# amp128-v5.net
KiCad netlist of a schematic drawn in EAGLE
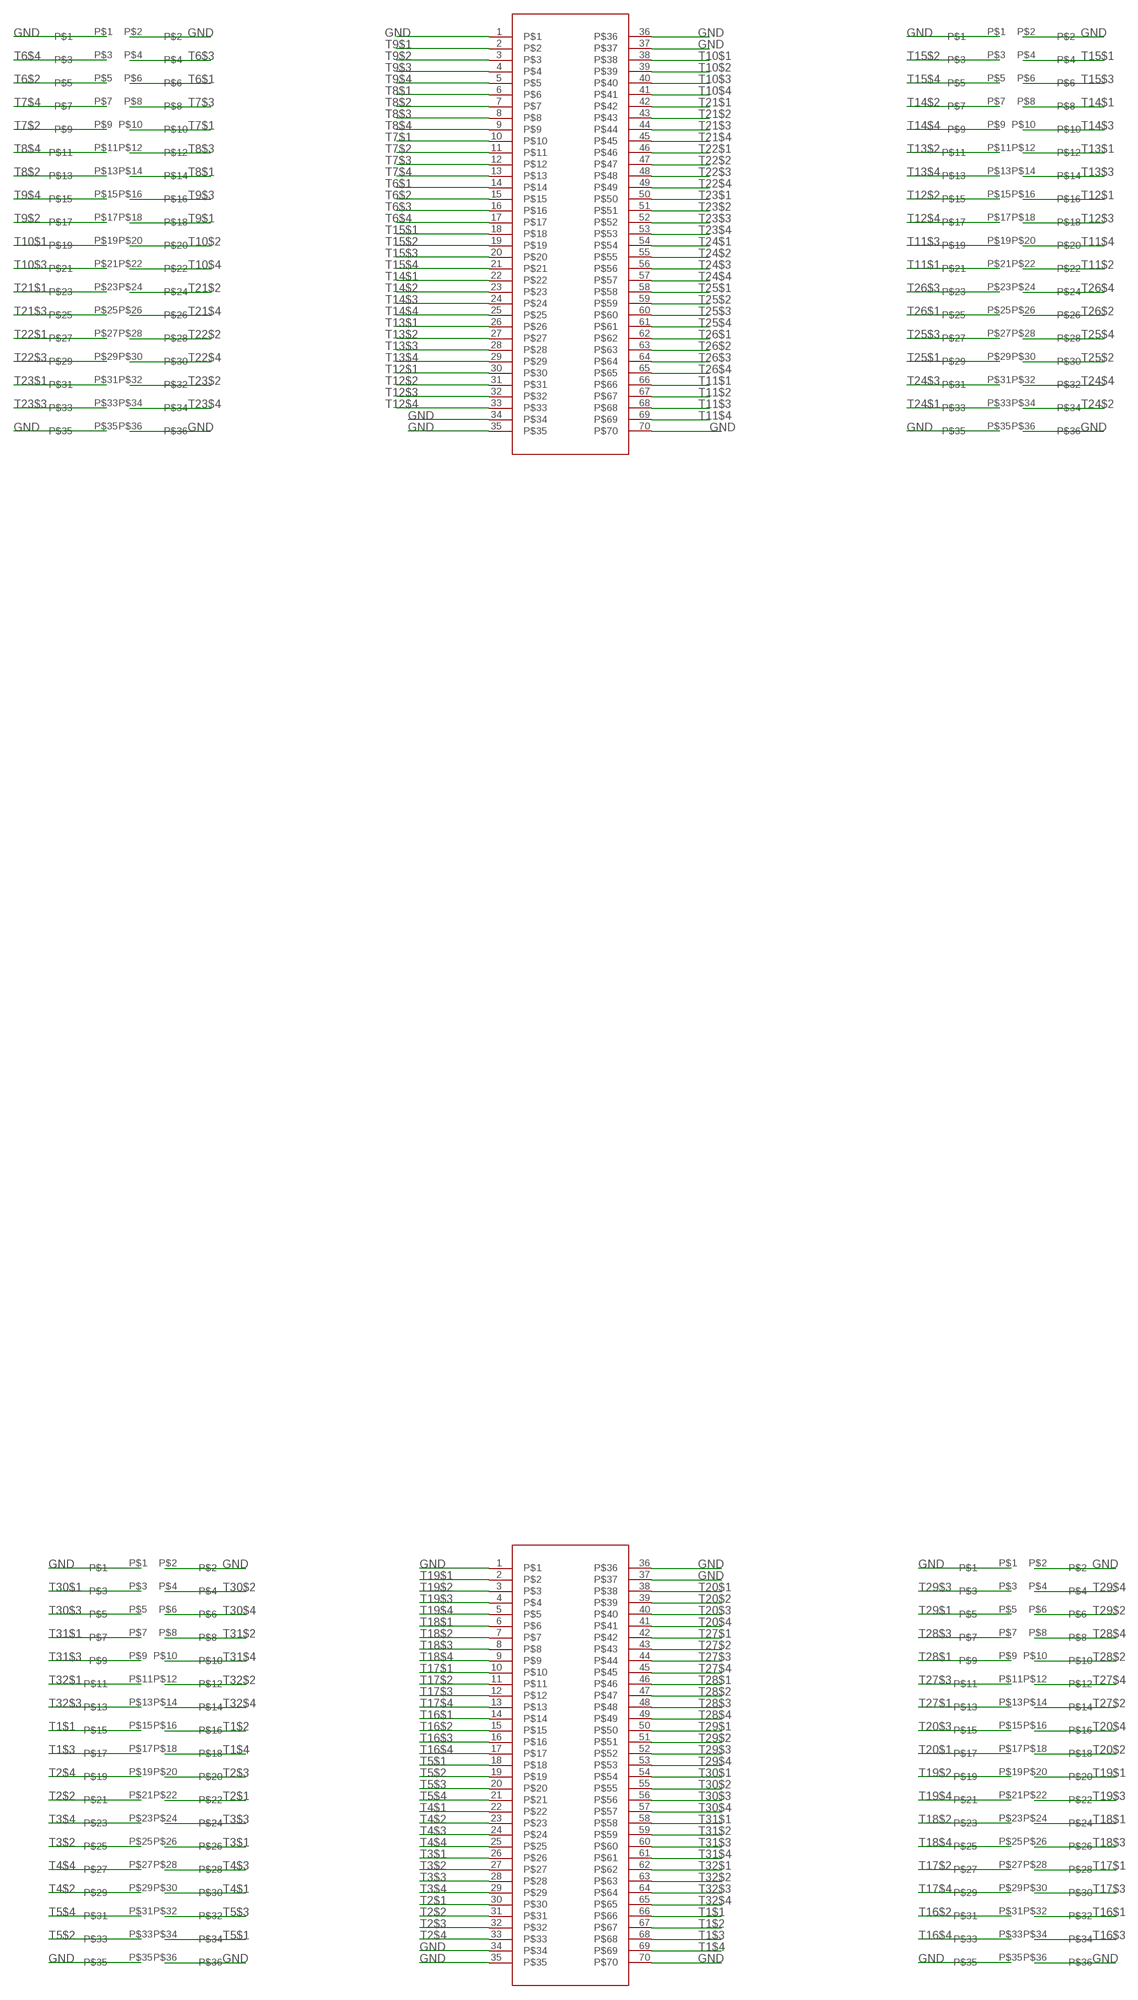
[diagram p0: schematic, sheet 1]

(export (version "E")
  (design (tool "Eeschema 10.0.6"))
  (components
    (comp (ref "U$1")
      (value "DF40C-70DS")
      (footprint "eagle-import:DF40C-70DS")
      (libsource (lib "eagle-import") (part "DF40C-70DS"))
    )
    (comp (ref "U$2")
      (value "DF40C-70DS")
      (footprint "eagle-import:DF40C-70DS")
      (libsource (lib "eagle-import") (part "DF40C-70DS"))
    )
    (comp (ref "U$3")
      (value "MILL-MAX2BY18")
      (footprint "eagle-import:MILL-MAX2BY18")
      (libsource (lib "eagle-import") (part "MILL-MAX2BY18"))
    )
    (comp (ref "U$4")
      (value "MILL-MAX2BY18")
      (footprint "eagle-import:MILL-MAX2BY18")
      (libsource (lib "eagle-import") (part "MILL-MAX2BY18"))
    )
    (comp (ref "U$5")
      (value "MILL-MAX2BY18")
      (footprint "eagle-import:MILL-MAX2BY18")
      (libsource (lib "eagle-import") (part "MILL-MAX2BY18"))
    )
    (comp (ref "U$6")
      (value "MILL-MAX2BY18")
      (footprint "eagle-import:MILL-MAX2BY18")
      (libsource (lib "eagle-import") (part "MILL-MAX2BY18"))
    )
  )
  (nets
    (net (code "1") (name "/GND") (class "Default")
      (node (ref "U$1") (pin "1") (pinfunction "P$1_1") (pintype "bidirectional"))
      (node (ref "U$1") (pin "34") (pinfunction "P$34_34") (pintype "bidirectional"))
      (node (ref "U$1") (pin "35") (pinfunction "P$35_35") (pintype "bidirectional"))
      (node (ref "U$1") (pin "36") (pinfunction "P$36_36") (pintype "bidirectional"))
      (node (ref "U$1") (pin "37") (pinfunction "P$37_37") (pintype "bidirectional"))
      (node (ref "U$1") (pin "70") (pinfunction "P$70_70") (pintype "bidirectional"))
      (node (ref "U$2") (pin "1") (pinfunction "P$1_1") (pintype "bidirectional"))
      (node (ref "U$2") (pin "34") (pinfunction "P$34_34") (pintype "bidirectional"))
      (node (ref "U$2") (pin "35") (pinfunction "P$35_35") (pintype "bidirectional"))
      (node (ref "U$2") (pin "36") (pinfunction "P$36_36") (pintype "bidirectional"))
      (node (ref "U$2") (pin "37") (pinfunction "P$37_37") (pintype "bidirectional"))
      (node (ref "U$2") (pin "70") (pinfunction "P$70_70") (pintype "bidirectional"))
      (node (ref "U$3") (pin "P$1") (pinfunction "P$1_P$1") (pintype "bidirectional"))
      (node (ref "U$3") (pin "P$2") (pinfunction "P$2_P$2") (pintype "bidirectional"))
      (node (ref "U$3") (pin "P$35") (pinfunction "P$35_P$35") (pintype "bidirectional"))
      (node (ref "U$3") (pin "P$36") (pinfunction "P$36_P$36") (pintype "bidirectional"))
      (node (ref "U$4") (pin "P$1") (pinfunction "P$1_P$1") (pintype "bidirectional"))
      (node (ref "U$4") (pin "P$2") (pinfunction "P$2_P$2") (pintype "bidirectional"))
      (node (ref "U$4") (pin "P$35") (pinfunction "P$35_P$35") (pintype "bidirectional"))
      (node (ref "U$4") (pin "P$36") (pinfunction "P$36_P$36") (pintype "bidirectional"))
      (node (ref "U$5") (pin "P$1") (pinfunction "P$1_P$1") (pintype "bidirectional"))
      (node (ref "U$5") (pin "P$2") (pinfunction "P$2_P$2") (pintype "bidirectional"))
      (node (ref "U$5") (pin "P$35") (pinfunction "P$35_P$35") (pintype "bidirectional"))
      (node (ref "U$5") (pin "P$36") (pinfunction "P$36_P$36") (pintype "bidirectional"))
      (node (ref "U$6") (pin "P$1") (pinfunction "P$1_P$1") (pintype "bidirectional"))
      (node (ref "U$6") (pin "P$2") (pinfunction "P$2_P$2") (pintype "bidirectional"))
      (node (ref "U$6") (pin "P$35") (pinfunction "P$35_P$35") (pintype "bidirectional"))
      (node (ref "U$6") (pin "P$36") (pinfunction "P$36_P$36") (pintype "bidirectional"))
    )
    (net (code "2") (name "/T1$1") (class "Default")
      (node (ref "U$2") (pin "66") (pinfunction "P$66_66") (pintype "bidirectional"))
      (node (ref "U$5") (pin "P$15") (pinfunction "P$15_P$15") (pintype "bidirectional"))
    )
    (net (code "3") (name "/T1$2") (class "Default")
      (node (ref "U$2") (pin "67") (pinfunction "P$67_67") (pintype "bidirectional"))
      (node (ref "U$5") (pin "P$16") (pinfunction "P$16_P$16") (pintype "bidirectional"))
    )
    (net (code "4") (name "/T1$3") (class "Default")
      (node (ref "U$2") (pin "68") (pinfunction "P$68_68") (pintype "bidirectional"))
      (node (ref "U$5") (pin "P$17") (pinfunction "P$17_P$17") (pintype "bidirectional"))
    )
    (net (code "5") (name "/T1$4") (class "Default")
      (node (ref "U$2") (pin "69") (pinfunction "P$69_69") (pintype "bidirectional"))
      (node (ref "U$5") (pin "P$18") (pinfunction "P$18_P$18") (pintype "bidirectional"))
    )
    (net (code "6") (name "/T2$1") (class "Default")
      (node (ref "U$2") (pin "30") (pinfunction "P$30_30") (pintype "bidirectional"))
      (node (ref "U$5") (pin "P$22") (pinfunction "P$22_P$22") (pintype "bidirectional"))
    )
    (net (code "7") (name "/T2$2") (class "Default")
      (node (ref "U$2") (pin "31") (pinfunction "P$31_31") (pintype "bidirectional"))
      (node (ref "U$5") (pin "P$21") (pinfunction "P$21_P$21") (pintype "bidirectional"))
    )
    (net (code "8") (name "/T2$3") (class "Default")
      (node (ref "U$2") (pin "32") (pinfunction "P$32_32") (pintype "bidirectional"))
      (node (ref "U$5") (pin "P$20") (pinfunction "P$20_P$20") (pintype "bidirectional"))
    )
    (net (code "9") (name "/T2$4") (class "Default")
      (node (ref "U$2") (pin "33") (pinfunction "P$33_33") (pintype "bidirectional"))
      (node (ref "U$5") (pin "P$19") (pinfunction "P$19_P$19") (pintype "bidirectional"))
    )
    (net (code "10") (name "/T3$1") (class "Default")
      (node (ref "U$2") (pin "26") (pinfunction "P$26_26") (pintype "bidirectional"))
      (node (ref "U$5") (pin "P$26") (pinfunction "P$26_P$26") (pintype "bidirectional"))
    )
    (net (code "11") (name "/T3$2") (class "Default")
      (node (ref "U$2") (pin "27") (pinfunction "P$27_27") (pintype "bidirectional"))
      (node (ref "U$5") (pin "P$25") (pinfunction "P$25_P$25") (pintype "bidirectional"))
    )
    (net (code "12") (name "/T3$3") (class "Default")
      (node (ref "U$2") (pin "28") (pinfunction "P$28_28") (pintype "bidirectional"))
      (node (ref "U$5") (pin "P$24") (pinfunction "P$24_P$24") (pintype "bidirectional"))
    )
    (net (code "13") (name "/T3$4") (class "Default")
      (node (ref "U$2") (pin "29") (pinfunction "P$29_29") (pintype "bidirectional"))
      (node (ref "U$5") (pin "P$23") (pinfunction "P$23_P$23") (pintype "bidirectional"))
    )
    (net (code "14") (name "/T4$1") (class "Default")
      (node (ref "U$2") (pin "22") (pinfunction "P$22_22") (pintype "bidirectional"))
      (node (ref "U$5") (pin "P$30") (pinfunction "P$30_P$30") (pintype "bidirectional"))
    )
    (net (code "15") (name "/T4$2") (class "Default")
      (node (ref "U$2") (pin "23") (pinfunction "P$23_23") (pintype "bidirectional"))
      (node (ref "U$5") (pin "P$29") (pinfunction "P$29_P$29") (pintype "bidirectional"))
    )
    (net (code "16") (name "/T4$3") (class "Default")
      (node (ref "U$2") (pin "24") (pinfunction "P$24_24") (pintype "bidirectional"))
      (node (ref "U$5") (pin "P$28") (pinfunction "P$28_P$28") (pintype "bidirectional"))
    )
    (net (code "17") (name "/T4$4") (class "Default")
      (node (ref "U$2") (pin "25") (pinfunction "P$25_25") (pintype "bidirectional"))
      (node (ref "U$5") (pin "P$27") (pinfunction "P$27_P$27") (pintype "bidirectional"))
    )
    (net (code "18") (name "/T5$1") (class "Default")
      (node (ref "U$2") (pin "18") (pinfunction "P$18_18") (pintype "bidirectional"))
      (node (ref "U$5") (pin "P$34") (pinfunction "P$34_P$34") (pintype "bidirectional"))
    )
    (net (code "19") (name "/T5$2") (class "Default")
      (node (ref "U$2") (pin "19") (pinfunction "P$19_19") (pintype "bidirectional"))
      (node (ref "U$5") (pin "P$33") (pinfunction "P$33_P$33") (pintype "bidirectional"))
    )
    (net (code "20") (name "/T5$3") (class "Default")
      (node (ref "U$2") (pin "20") (pinfunction "P$20_20") (pintype "bidirectional"))
      (node (ref "U$5") (pin "P$32") (pinfunction "P$32_P$32") (pintype "bidirectional"))
    )
    (net (code "21") (name "/T5$4") (class "Default")
      (node (ref "U$2") (pin "21") (pinfunction "P$21_21") (pintype "bidirectional"))
      (node (ref "U$5") (pin "P$31") (pinfunction "P$31_P$31") (pintype "bidirectional"))
    )
    (net (code "22") (name "/T6$1") (class "Default")
      (node (ref "U$1") (pin "14") (pinfunction "P$14_14") (pintype "bidirectional"))
      (node (ref "U$3") (pin "P$6") (pinfunction "P$6_P$6") (pintype "bidirectional"))
    )
    (net (code "23") (name "/T6$2") (class "Default")
      (node (ref "U$1") (pin "15") (pinfunction "P$15_15") (pintype "bidirectional"))
      (node (ref "U$3") (pin "P$5") (pinfunction "P$5_P$5") (pintype "bidirectional"))
    )
    (net (code "24") (name "/T6$3") (class "Default")
      (node (ref "U$1") (pin "16") (pinfunction "P$16_16") (pintype "bidirectional"))
      (node (ref "U$3") (pin "P$4") (pinfunction "P$4_P$4") (pintype "bidirectional"))
    )
    (net (code "25") (name "/T6$4") (class "Default")
      (node (ref "U$1") (pin "17") (pinfunction "P$17_17") (pintype "bidirectional"))
      (node (ref "U$3") (pin "P$3") (pinfunction "P$3_P$3") (pintype "bidirectional"))
    )
    (net (code "26") (name "/T7$1") (class "Default")
      (node (ref "U$1") (pin "10") (pinfunction "P$10_10") (pintype "bidirectional"))
      (node (ref "U$3") (pin "P$10") (pinfunction "P$10_P$10") (pintype "bidirectional"))
    )
    (net (code "27") (name "/T7$2") (class "Default")
      (node (ref "U$1") (pin "11") (pinfunction "P$11_11") (pintype "bidirectional"))
      (node (ref "U$3") (pin "P$9") (pinfunction "P$9_P$9") (pintype "bidirectional"))
    )
    (net (code "28") (name "/T7$3") (class "Default")
      (node (ref "U$1") (pin "12") (pinfunction "P$12_12") (pintype "bidirectional"))
      (node (ref "U$3") (pin "P$8") (pinfunction "P$8_P$8") (pintype "bidirectional"))
    )
    (net (code "29") (name "/T7$4") (class "Default")
      (node (ref "U$1") (pin "13") (pinfunction "P$13_13") (pintype "bidirectional"))
      (node (ref "U$3") (pin "P$7") (pinfunction "P$7_P$7") (pintype "bidirectional"))
    )
    (net (code "30") (name "/T8$1") (class "Default")
      (node (ref "U$1") (pin "6") (pinfunction "P$6_6") (pintype "bidirectional"))
      (node (ref "U$3") (pin "P$14") (pinfunction "P$14_P$14") (pintype "bidirectional"))
    )
    (net (code "31") (name "/T8$2") (class "Default")
      (node (ref "U$1") (pin "7") (pinfunction "P$7_7") (pintype "bidirectional"))
      (node (ref "U$3") (pin "P$13") (pinfunction "P$13_P$13") (pintype "bidirectional"))
    )
    (net (code "32") (name "/T8$3") (class "Default")
      (node (ref "U$1") (pin "8") (pinfunction "P$8_8") (pintype "bidirectional"))
      (node (ref "U$3") (pin "P$12") (pinfunction "P$12_P$12") (pintype "bidirectional"))
    )
    (net (code "33") (name "/T8$4") (class "Default")
      (node (ref "U$1") (pin "9") (pinfunction "P$9_9") (pintype "bidirectional"))
      (node (ref "U$3") (pin "P$11") (pinfunction "P$11_P$11") (pintype "bidirectional"))
    )
    (net (code "34") (name "/T9$1") (class "Default")
      (node (ref "U$1") (pin "2") (pinfunction "P$2_2") (pintype "bidirectional"))
      (node (ref "U$3") (pin "P$18") (pinfunction "P$18_P$18") (pintype "bidirectional"))
    )
    (net (code "35") (name "/T9$2") (class "Default")
      (node (ref "U$1") (pin "3") (pinfunction "P$3_3") (pintype "bidirectional"))
      (node (ref "U$3") (pin "P$17") (pinfunction "P$17_P$17") (pintype "bidirectional"))
    )
    (net (code "36") (name "/T9$3") (class "Default")
      (node (ref "U$1") (pin "4") (pinfunction "P$4_4") (pintype "bidirectional"))
      (node (ref "U$3") (pin "P$16") (pinfunction "P$16_P$16") (pintype "bidirectional"))
    )
    (net (code "37") (name "/T9$4") (class "Default")
      (node (ref "U$1") (pin "5") (pinfunction "P$5_5") (pintype "bidirectional"))
      (node (ref "U$3") (pin "P$15") (pinfunction "P$15_P$15") (pintype "bidirectional"))
    )
    (net (code "38") (name "/T10$1") (class "Default")
      (node (ref "U$1") (pin "38") (pinfunction "P$38_38") (pintype "bidirectional"))
      (node (ref "U$3") (pin "P$19") (pinfunction "P$19_P$19") (pintype "bidirectional"))
    )
    (net (code "39") (name "/T10$2") (class "Default")
      (node (ref "U$1") (pin "39") (pinfunction "P$39_39") (pintype "bidirectional"))
      (node (ref "U$3") (pin "P$20") (pinfunction "P$20_P$20") (pintype "bidirectional"))
    )
    (net (code "40") (name "/T10$3") (class "Default")
      (node (ref "U$1") (pin "40") (pinfunction "P$40_40") (pintype "bidirectional"))
      (node (ref "U$3") (pin "P$21") (pinfunction "P$21_P$21") (pintype "bidirectional"))
    )
    (net (code "41") (name "/T10$4") (class "Default")
      (node (ref "U$1") (pin "41") (pinfunction "P$41_41") (pintype "bidirectional"))
      (node (ref "U$3") (pin "P$22") (pinfunction "P$22_P$22") (pintype "bidirectional"))
    )
    (net (code "42") (name "/T11$1") (class "Default")
      (node (ref "U$1") (pin "66") (pinfunction "P$66_66") (pintype "bidirectional"))
      (node (ref "U$4") (pin "P$21") (pinfunction "P$21_P$21") (pintype "bidirectional"))
    )
    (net (code "43") (name "/T11$2") (class "Default")
      (node (ref "U$1") (pin "67") (pinfunction "P$67_67") (pintype "bidirectional"))
      (node (ref "U$4") (pin "P$22") (pinfunction "P$22_P$22") (pintype "bidirectional"))
    )
    (net (code "44") (name "/T11$3") (class "Default")
      (node (ref "U$1") (pin "68") (pinfunction "P$68_68") (pintype "bidirectional"))
      (node (ref "U$4") (pin "P$19") (pinfunction "P$19_P$19") (pintype "bidirectional"))
    )
    (net (code "45") (name "/T11$4") (class "Default")
      (node (ref "U$1") (pin "69") (pinfunction "P$69_69") (pintype "bidirectional"))
      (node (ref "U$4") (pin "P$20") (pinfunction "P$20_P$20") (pintype "bidirectional"))
    )
    (net (code "46") (name "/T12$1") (class "Default")
      (node (ref "U$1") (pin "30") (pinfunction "P$30_30") (pintype "bidirectional"))
      (node (ref "U$4") (pin "P$16") (pinfunction "P$16_P$16") (pintype "bidirectional"))
    )
    (net (code "47") (name "/T12$2") (class "Default")
      (node (ref "U$1") (pin "31") (pinfunction "P$31_31") (pintype "bidirectional"))
      (node (ref "U$4") (pin "P$15") (pinfunction "P$15_P$15") (pintype "bidirectional"))
    )
    (net (code "48") (name "/T12$3") (class "Default")
      (node (ref "U$1") (pin "32") (pinfunction "P$32_32") (pintype "bidirectional"))
      (node (ref "U$4") (pin "P$18") (pinfunction "P$18_P$18") (pintype "bidirectional"))
    )
    (net (code "49") (name "/T12$4") (class "Default")
      (node (ref "U$1") (pin "33") (pinfunction "P$33_33") (pintype "bidirectional"))
      (node (ref "U$4") (pin "P$17") (pinfunction "P$17_P$17") (pintype "bidirectional"))
    )
    (net (code "50") (name "/T13$1") (class "Default")
      (node (ref "U$1") (pin "26") (pinfunction "P$26_26") (pintype "bidirectional"))
      (node (ref "U$4") (pin "P$12") (pinfunction "P$12_P$12") (pintype "bidirectional"))
    )
    (net (code "51") (name "/T13$2") (class "Default")
      (node (ref "U$1") (pin "27") (pinfunction "P$27_27") (pintype "bidirectional"))
      (node (ref "U$4") (pin "P$11") (pinfunction "P$11_P$11") (pintype "bidirectional"))
    )
    (net (code "52") (name "/T13$3") (class "Default")
      (node (ref "U$1") (pin "28") (pinfunction "P$28_28") (pintype "bidirectional"))
      (node (ref "U$4") (pin "P$14") (pinfunction "P$14_P$14") (pintype "bidirectional"))
    )
    (net (code "53") (name "/T13$4") (class "Default")
      (node (ref "U$1") (pin "29") (pinfunction "P$29_29") (pintype "bidirectional"))
      (node (ref "U$4") (pin "P$13") (pinfunction "P$13_P$13") (pintype "bidirectional"))
    )
    (net (code "54") (name "/T14$1") (class "Default")
      (node (ref "U$1") (pin "22") (pinfunction "P$22_22") (pintype "bidirectional"))
      (node (ref "U$4") (pin "P$8") (pinfunction "P$8_P$8") (pintype "bidirectional"))
    )
    (net (code "55") (name "/T14$2") (class "Default")
      (node (ref "U$1") (pin "23") (pinfunction "P$23_23") (pintype "bidirectional"))
      (node (ref "U$4") (pin "P$7") (pinfunction "P$7_P$7") (pintype "bidirectional"))
    )
    (net (code "56") (name "/T14$3") (class "Default")
      (node (ref "U$1") (pin "24") (pinfunction "P$24_24") (pintype "bidirectional"))
      (node (ref "U$4") (pin "P$10") (pinfunction "P$10_P$10") (pintype "bidirectional"))
    )
    (net (code "57") (name "/T14$4") (class "Default")
      (node (ref "U$1") (pin "25") (pinfunction "P$25_25") (pintype "bidirectional"))
      (node (ref "U$4") (pin "P$9") (pinfunction "P$9_P$9") (pintype "bidirectional"))
    )
    (net (code "58") (name "/T15$1") (class "Default")
      (node (ref "U$1") (pin "18") (pinfunction "P$18_18") (pintype "bidirectional"))
      (node (ref "U$4") (pin "P$4") (pinfunction "P$4_P$4") (pintype "bidirectional"))
    )
    (net (code "59") (name "/T15$2") (class "Default")
      (node (ref "U$1") (pin "19") (pinfunction "P$19_19") (pintype "bidirectional"))
      (node (ref "U$4") (pin "P$3") (pinfunction "P$3_P$3") (pintype "bidirectional"))
    )
    (net (code "60") (name "/T15$3") (class "Default")
      (node (ref "U$1") (pin "20") (pinfunction "P$20_20") (pintype "bidirectional"))
      (node (ref "U$4") (pin "P$6") (pinfunction "P$6_P$6") (pintype "bidirectional"))
    )
    (net (code "61") (name "/T15$4") (class "Default")
      (node (ref "U$1") (pin "21") (pinfunction "P$21_21") (pintype "bidirectional"))
      (node (ref "U$4") (pin "P$5") (pinfunction "P$5_P$5") (pintype "bidirectional"))
    )
    (net (code "62") (name "/T16$1") (class "Default")
      (node (ref "U$2") (pin "14") (pinfunction "P$14_14") (pintype "bidirectional"))
      (node (ref "U$6") (pin "P$32") (pinfunction "P$32_P$32") (pintype "bidirectional"))
    )
    (net (code "63") (name "/T16$2") (class "Default")
      (node (ref "U$2") (pin "15") (pinfunction "P$15_15") (pintype "bidirectional"))
      (node (ref "U$6") (pin "P$31") (pinfunction "P$31_P$31") (pintype "bidirectional"))
    )
    (net (code "64") (name "/T16$3") (class "Default")
      (node (ref "U$2") (pin "16") (pinfunction "P$16_16") (pintype "bidirectional"))
      (node (ref "U$6") (pin "P$34") (pinfunction "P$34_P$34") (pintype "bidirectional"))
    )
    (net (code "65") (name "/T16$4") (class "Default")
      (node (ref "U$2") (pin "17") (pinfunction "P$17_17") (pintype "bidirectional"))
      (node (ref "U$6") (pin "P$33") (pinfunction "P$33_P$33") (pintype "bidirectional"))
    )
    (net (code "66") (name "/T17$1") (class "Default")
      (node (ref "U$2") (pin "10") (pinfunction "P$10_10") (pintype "bidirectional"))
      (node (ref "U$6") (pin "P$28") (pinfunction "P$28_P$28") (pintype "bidirectional"))
    )
    (net (code "67") (name "/T17$2") (class "Default")
      (node (ref "U$2") (pin "11") (pinfunction "P$11_11") (pintype "bidirectional"))
      (node (ref "U$6") (pin "P$27") (pinfunction "P$27_P$27") (pintype "bidirectional"))
    )
    (net (code "68") (name "/T17$3") (class "Default")
      (node (ref "U$2") (pin "12") (pinfunction "P$12_12") (pintype "bidirectional"))
      (node (ref "U$6") (pin "P$30") (pinfunction "P$30_P$30") (pintype "bidirectional"))
    )
    (net (code "69") (name "/T17$4") (class "Default")
      (node (ref "U$2") (pin "13") (pinfunction "P$13_13") (pintype "bidirectional"))
      (node (ref "U$6") (pin "P$29") (pinfunction "P$29_P$29") (pintype "bidirectional"))
    )
    (net (code "70") (name "/T18$1") (class "Default")
      (node (ref "U$2") (pin "6") (pinfunction "P$6_6") (pintype "bidirectional"))
      (node (ref "U$6") (pin "P$24") (pinfunction "P$24_P$24") (pintype "bidirectional"))
    )
    (net (code "71") (name "/T18$2") (class "Default")
      (node (ref "U$2") (pin "7") (pinfunction "P$7_7") (pintype "bidirectional"))
      (node (ref "U$6") (pin "P$23") (pinfunction "P$23_P$23") (pintype "bidirectional"))
    )
    (net (code "72") (name "/T18$3") (class "Default")
      (node (ref "U$2") (pin "8") (pinfunction "P$8_8") (pintype "bidirectional"))
      (node (ref "U$6") (pin "P$26") (pinfunction "P$26_P$26") (pintype "bidirectional"))
    )
    (net (code "73") (name "/T18$4") (class "Default")
      (node (ref "U$2") (pin "9") (pinfunction "P$9_9") (pintype "bidirectional"))
      (node (ref "U$6") (pin "P$25") (pinfunction "P$25_P$25") (pintype "bidirectional"))
    )
    (net (code "74") (name "/T19$1") (class "Default")
      (node (ref "U$2") (pin "2") (pinfunction "P$2_2") (pintype "bidirectional"))
      (node (ref "U$6") (pin "P$20") (pinfunction "P$20_P$20") (pintype "bidirectional"))
    )
    (net (code "75") (name "/T19$2") (class "Default")
      (node (ref "U$2") (pin "3") (pinfunction "P$3_3") (pintype "bidirectional"))
      (node (ref "U$6") (pin "P$19") (pinfunction "P$19_P$19") (pintype "bidirectional"))
    )
    (net (code "76") (name "/T19$3") (class "Default")
      (node (ref "U$2") (pin "4") (pinfunction "P$4_4") (pintype "bidirectional"))
      (node (ref "U$6") (pin "P$22") (pinfunction "P$22_P$22") (pintype "bidirectional"))
    )
    (net (code "77") (name "/T19$4") (class "Default")
      (node (ref "U$2") (pin "5") (pinfunction "P$5_5") (pintype "bidirectional"))
      (node (ref "U$6") (pin "P$21") (pinfunction "P$21_P$21") (pintype "bidirectional"))
    )
    (net (code "78") (name "/T20$1") (class "Default")
      (node (ref "U$2") (pin "38") (pinfunction "P$38_38") (pintype "bidirectional"))
      (node (ref "U$6") (pin "P$17") (pinfunction "P$17_P$17") (pintype "bidirectional"))
    )
    (net (code "79") (name "/T20$2") (class "Default")
      (node (ref "U$2") (pin "39") (pinfunction "P$39_39") (pintype "bidirectional"))
      (node (ref "U$6") (pin "P$18") (pinfunction "P$18_P$18") (pintype "bidirectional"))
    )
    (net (code "80") (name "/T20$3") (class "Default")
      (node (ref "U$2") (pin "40") (pinfunction "P$40_40") (pintype "bidirectional"))
      (node (ref "U$6") (pin "P$15") (pinfunction "P$15_P$15") (pintype "bidirectional"))
    )
    (net (code "81") (name "/T20$4") (class "Default")
      (node (ref "U$2") (pin "41") (pinfunction "P$41_41") (pintype "bidirectional"))
      (node (ref "U$6") (pin "P$16") (pinfunction "P$16_P$16") (pintype "bidirectional"))
    )
    (net (code "82") (name "/T21$1") (class "Default")
      (node (ref "U$1") (pin "42") (pinfunction "P$42_42") (pintype "bidirectional"))
      (node (ref "U$3") (pin "P$23") (pinfunction "P$23_P$23") (pintype "bidirectional"))
    )
    (net (code "83") (name "/T21$2") (class "Default")
      (node (ref "U$1") (pin "43") (pinfunction "P$43_43") (pintype "bidirectional"))
      (node (ref "U$3") (pin "P$24") (pinfunction "P$24_P$24") (pintype "bidirectional"))
    )
    (net (code "84") (name "/T21$3") (class "Default")
      (node (ref "U$1") (pin "44") (pinfunction "P$44_44") (pintype "bidirectional"))
      (node (ref "U$3") (pin "P$25") (pinfunction "P$25_P$25") (pintype "bidirectional"))
    )
    (net (code "85") (name "/T21$4") (class "Default")
      (node (ref "U$1") (pin "45") (pinfunction "P$45_45") (pintype "bidirectional"))
      (node (ref "U$3") (pin "P$26") (pinfunction "P$26_P$26") (pintype "bidirectional"))
    )
    (net (code "86") (name "/T22$1") (class "Default")
      (node (ref "U$1") (pin "46") (pinfunction "P$46_46") (pintype "bidirectional"))
      (node (ref "U$3") (pin "P$27") (pinfunction "P$27_P$27") (pintype "bidirectional"))
    )
    (net (code "87") (name "/T22$2") (class "Default")
      (node (ref "U$1") (pin "47") (pinfunction "P$47_47") (pintype "bidirectional"))
      (node (ref "U$3") (pin "P$28") (pinfunction "P$28_P$28") (pintype "bidirectional"))
    )
    (net (code "88") (name "/T22$3") (class "Default")
      (node (ref "U$1") (pin "48") (pinfunction "P$48_48") (pintype "bidirectional"))
      (node (ref "U$3") (pin "P$29") (pinfunction "P$29_P$29") (pintype "bidirectional"))
    )
    (net (code "89") (name "/T22$4") (class "Default")
      (node (ref "U$1") (pin "49") (pinfunction "P$49_49") (pintype "bidirectional"))
      (node (ref "U$3") (pin "P$30") (pinfunction "P$30_P$30") (pintype "bidirectional"))
    )
    (net (code "90") (name "/T23$1") (class "Default")
      (node (ref "U$1") (pin "50") (pinfunction "P$50_50") (pintype "bidirectional"))
      (node (ref "U$3") (pin "P$31") (pinfunction "P$31_P$31") (pintype "bidirectional"))
    )
    (net (code "91") (name "/T23$2") (class "Default")
      (node (ref "U$1") (pin "51") (pinfunction "P$51_51") (pintype "bidirectional"))
      (node (ref "U$3") (pin "P$32") (pinfunction "P$32_P$32") (pintype "bidirectional"))
    )
    (net (code "92") (name "/T23$3") (class "Default")
      (node (ref "U$1") (pin "52") (pinfunction "P$52_52") (pintype "bidirectional"))
      (node (ref "U$3") (pin "P$33") (pinfunction "P$33_P$33") (pintype "bidirectional"))
    )
    (net (code "93") (name "/T23$4") (class "Default")
      (node (ref "U$1") (pin "53") (pinfunction "P$53_53") (pintype "bidirectional"))
      (node (ref "U$3") (pin "P$34") (pinfunction "P$34_P$34") (pintype "bidirectional"))
    )
    (net (code "94") (name "/T24$1") (class "Default")
      (node (ref "U$1") (pin "54") (pinfunction "P$54_54") (pintype "bidirectional"))
      (node (ref "U$4") (pin "P$33") (pinfunction "P$33_P$33") (pintype "bidirectional"))
    )
    (net (code "95") (name "/T24$2") (class "Default")
      (node (ref "U$1") (pin "55") (pinfunction "P$55_55") (pintype "bidirectional"))
      (node (ref "U$4") (pin "P$34") (pinfunction "P$34_P$34") (pintype "bidirectional"))
    )
    (net (code "96") (name "/T24$3") (class "Default")
      (node (ref "U$1") (pin "56") (pinfunction "P$56_56") (pintype "bidirectional"))
      (node (ref "U$4") (pin "P$31") (pinfunction "P$31_P$31") (pintype "bidirectional"))
    )
    (net (code "97") (name "/T24$4") (class "Default")
      (node (ref "U$1") (pin "57") (pinfunction "P$57_57") (pintype "bidirectional"))
      (node (ref "U$4") (pin "P$32") (pinfunction "P$32_P$32") (pintype "bidirectional"))
    )
    (net (code "98") (name "/T25$1") (class "Default")
      (node (ref "U$1") (pin "58") (pinfunction "P$58_58") (pintype "bidirectional"))
      (node (ref "U$4") (pin "P$29") (pinfunction "P$29_P$29") (pintype "bidirectional"))
    )
    (net (code "99") (name "/T25$2") (class "Default")
      (node (ref "U$1") (pin "59") (pinfunction "P$59_59") (pintype "bidirectional"))
      (node (ref "U$4") (pin "P$30") (pinfunction "P$30_P$30") (pintype "bidirectional"))
    )
    (net (code "100") (name "/T25$3") (class "Default")
      (node (ref "U$1") (pin "60") (pinfunction "P$60_60") (pintype "bidirectional"))
      (node (ref "U$4") (pin "P$27") (pinfunction "P$27_P$27") (pintype "bidirectional"))
    )
    (net (code "101") (name "/T25$4") (class "Default")
      (node (ref "U$1") (pin "61") (pinfunction "P$61_61") (pintype "bidirectional"))
      (node (ref "U$4") (pin "P$28") (pinfunction "P$28_P$28") (pintype "bidirectional"))
    )
    (net (code "102") (name "/T26$1") (class "Default")
      (node (ref "U$1") (pin "62") (pinfunction "P$62_62") (pintype "bidirectional"))
      (node (ref "U$4") (pin "P$25") (pinfunction "P$25_P$25") (pintype "bidirectional"))
    )
    (net (code "103") (name "/T26$2") (class "Default")
      (node (ref "U$1") (pin "63") (pinfunction "P$63_63") (pintype "bidirectional"))
      (node (ref "U$4") (pin "P$26") (pinfunction "P$26_P$26") (pintype "bidirectional"))
    )
    (net (code "104") (name "/T26$3") (class "Default")
      (node (ref "U$1") (pin "64") (pinfunction "P$64_64") (pintype "bidirectional"))
      (node (ref "U$4") (pin "P$23") (pinfunction "P$23_P$23") (pintype "bidirectional"))
    )
    (net (code "105") (name "/T26$4") (class "Default")
      (node (ref "U$1") (pin "65") (pinfunction "P$65_65") (pintype "bidirectional"))
      (node (ref "U$4") (pin "P$24") (pinfunction "P$24_P$24") (pintype "bidirectional"))
    )
    (net (code "106") (name "/T27$1") (class "Default")
      (node (ref "U$2") (pin "42") (pinfunction "P$42_42") (pintype "bidirectional"))
      (node (ref "U$6") (pin "P$13") (pinfunction "P$13_P$13") (pintype "bidirectional"))
    )
    (net (code "107") (name "/T27$2") (class "Default")
      (node (ref "U$2") (pin "43") (pinfunction "P$43_43") (pintype "bidirectional"))
      (node (ref "U$6") (pin "P$14") (pinfunction "P$14_P$14") (pintype "bidirectional"))
    )
    (net (code "108") (name "/T27$3") (class "Default")
      (node (ref "U$2") (pin "44") (pinfunction "P$44_44") (pintype "bidirectional"))
      (node (ref "U$6") (pin "P$11") (pinfunction "P$11_P$11") (pintype "bidirectional"))
    )
    (net (code "109") (name "/T27$4") (class "Default")
      (node (ref "U$2") (pin "45") (pinfunction "P$45_45") (pintype "bidirectional"))
      (node (ref "U$6") (pin "P$12") (pinfunction "P$12_P$12") (pintype "bidirectional"))
    )
    (net (code "110") (name "/T28$1") (class "Default")
      (node (ref "U$2") (pin "46") (pinfunction "P$46_46") (pintype "bidirectional"))
      (node (ref "U$6") (pin "P$9") (pinfunction "P$9_P$9") (pintype "bidirectional"))
    )
    (net (code "111") (name "/T28$2") (class "Default")
      (node (ref "U$2") (pin "47") (pinfunction "P$47_47") (pintype "bidirectional"))
      (node (ref "U$6") (pin "P$10") (pinfunction "P$10_P$10") (pintype "bidirectional"))
    )
    (net (code "112") (name "/T28$3") (class "Default")
      (node (ref "U$2") (pin "48") (pinfunction "P$48_48") (pintype "bidirectional"))
      (node (ref "U$6") (pin "P$7") (pinfunction "P$7_P$7") (pintype "bidirectional"))
    )
    (net (code "113") (name "/T28$4") (class "Default")
      (node (ref "U$2") (pin "49") (pinfunction "P$49_49") (pintype "bidirectional"))
      (node (ref "U$6") (pin "P$8") (pinfunction "P$8_P$8") (pintype "bidirectional"))
    )
    (net (code "114") (name "/T29$1") (class "Default")
      (node (ref "U$2") (pin "50") (pinfunction "P$50_50") (pintype "bidirectional"))
      (node (ref "U$6") (pin "P$5") (pinfunction "P$5_P$5") (pintype "bidirectional"))
    )
    (net (code "115") (name "/T29$2") (class "Default")
      (node (ref "U$2") (pin "51") (pinfunction "P$51_51") (pintype "bidirectional"))
      (node (ref "U$6") (pin "P$6") (pinfunction "P$6_P$6") (pintype "bidirectional"))
    )
    (net (code "116") (name "/T29$3") (class "Default")
      (node (ref "U$2") (pin "52") (pinfunction "P$52_52") (pintype "bidirectional"))
      (node (ref "U$6") (pin "P$3") (pinfunction "P$3_P$3") (pintype "bidirectional"))
    )
    (net (code "117") (name "/T29$4") (class "Default")
      (node (ref "U$2") (pin "53") (pinfunction "P$53_53") (pintype "bidirectional"))
      (node (ref "U$6") (pin "P$4") (pinfunction "P$4_P$4") (pintype "bidirectional"))
    )
    (net (code "118") (name "/T30$1") (class "Default")
      (node (ref "U$2") (pin "54") (pinfunction "P$54_54") (pintype "bidirectional"))
      (node (ref "U$5") (pin "P$3") (pinfunction "P$3_P$3") (pintype "bidirectional"))
    )
    (net (code "119") (name "/T30$2") (class "Default")
      (node (ref "U$2") (pin "55") (pinfunction "P$55_55") (pintype "bidirectional"))
      (node (ref "U$5") (pin "P$4") (pinfunction "P$4_P$4") (pintype "bidirectional"))
    )
    (net (code "120") (name "/T30$3") (class "Default")
      (node (ref "U$2") (pin "56") (pinfunction "P$56_56") (pintype "bidirectional"))
      (node (ref "U$5") (pin "P$5") (pinfunction "P$5_P$5") (pintype "bidirectional"))
    )
    (net (code "121") (name "/T30$4") (class "Default")
      (node (ref "U$2") (pin "57") (pinfunction "P$57_57") (pintype "bidirectional"))
      (node (ref "U$5") (pin "P$6") (pinfunction "P$6_P$6") (pintype "bidirectional"))
    )
    (net (code "122") (name "/T31$1") (class "Default")
      (node (ref "U$2") (pin "58") (pinfunction "P$58_58") (pintype "bidirectional"))
      (node (ref "U$5") (pin "P$7") (pinfunction "P$7_P$7") (pintype "bidirectional"))
    )
    (net (code "123") (name "/T31$2") (class "Default")
      (node (ref "U$2") (pin "59") (pinfunction "P$59_59") (pintype "bidirectional"))
      (node (ref "U$5") (pin "P$8") (pinfunction "P$8_P$8") (pintype "bidirectional"))
    )
    (net (code "124") (name "/T31$3") (class "Default")
      (node (ref "U$2") (pin "60") (pinfunction "P$60_60") (pintype "bidirectional"))
      (node (ref "U$5") (pin "P$9") (pinfunction "P$9_P$9") (pintype "bidirectional"))
    )
    (net (code "125") (name "/T31$4") (class "Default")
      (node (ref "U$2") (pin "61") (pinfunction "P$61_61") (pintype "bidirectional"))
      (node (ref "U$5") (pin "P$10") (pinfunction "P$10_P$10") (pintype "bidirectional"))
    )
    (net (code "126") (name "/T32$1") (class "Default")
      (node (ref "U$2") (pin "62") (pinfunction "P$62_62") (pintype "bidirectional"))
      (node (ref "U$5") (pin "P$11") (pinfunction "P$11_P$11") (pintype "bidirectional"))
    )
    (net (code "127") (name "/T32$2") (class "Default")
      (node (ref "U$2") (pin "63") (pinfunction "P$63_63") (pintype "bidirectional"))
      (node (ref "U$5") (pin "P$12") (pinfunction "P$12_P$12") (pintype "bidirectional"))
    )
    (net (code "128") (name "/T32$3") (class "Default")
      (node (ref "U$2") (pin "64") (pinfunction "P$64_64") (pintype "bidirectional"))
      (node (ref "U$5") (pin "P$13") (pinfunction "P$13_P$13") (pintype "bidirectional"))
    )
    (net (code "129") (name "/T32$4") (class "Default")
      (node (ref "U$2") (pin "65") (pinfunction "P$65_65") (pintype "bidirectional"))
      (node (ref "U$5") (pin "P$14") (pinfunction "P$14_P$14") (pintype "bidirectional"))
    )
  )
)
